# Blocky_Uno.net
KiCad netlist of a schematic drawn in EAGLE
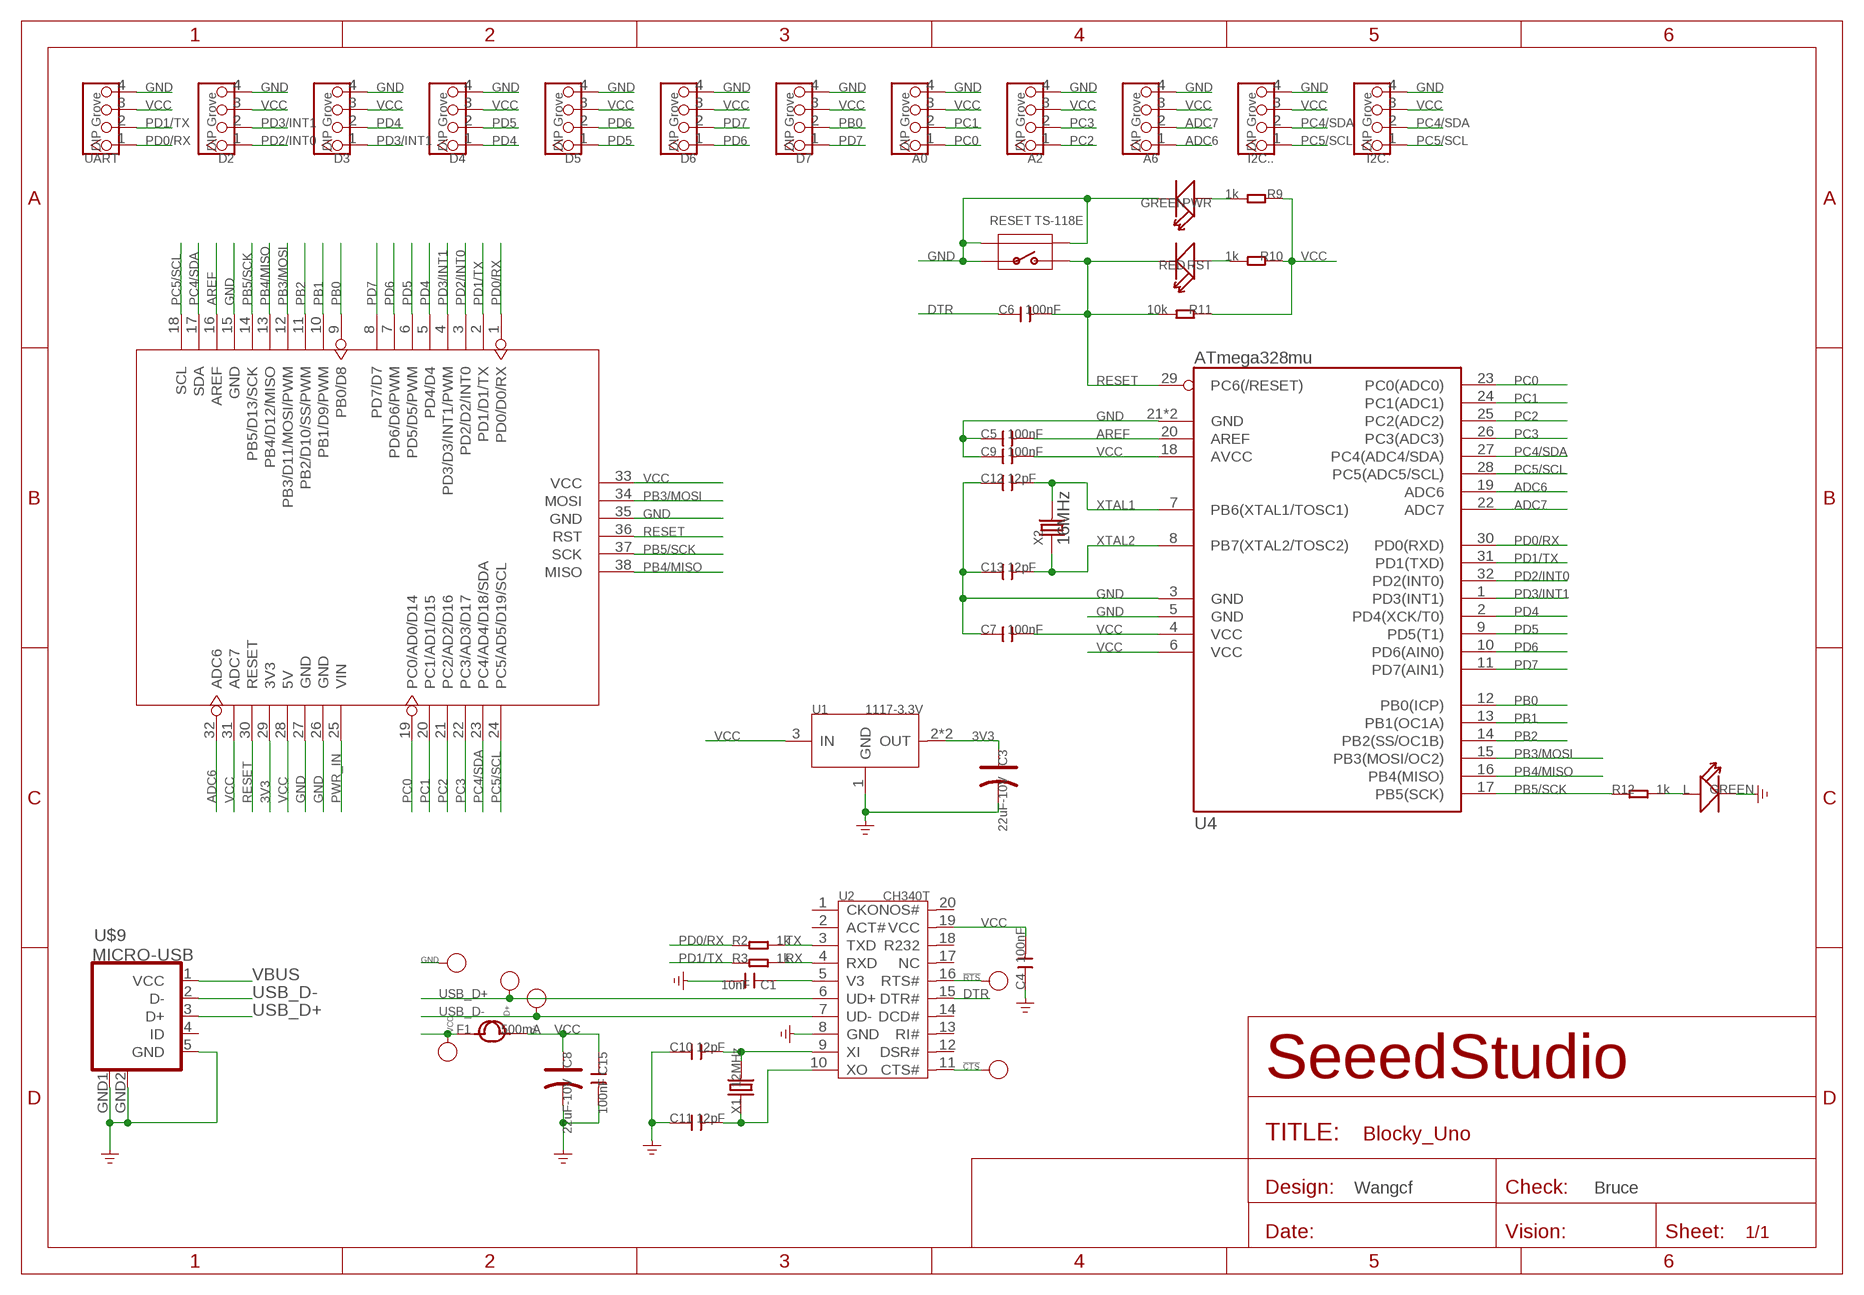
[diagram p0: schematic, sheet 1]

(export (version "E")
  (design (tool "Eeschema 10.0.6"))
  (components
    (comp (ref "!CTS")
      (value "PAD-TEST-POINT'4545'")
      (footprint "eagle-import:TP_4545")
      (fields (field (name "PARTNO") "DNP"))
      (libsource (lib "eagle-import") (part "PAD-TEST-POINT'4545'"))
    )
    (comp (ref "!RTS")
      (value "PAD-TEST-POINT'4545'")
      (footprint "eagle-import:TP_4545")
      (fields (field (name "PARTNO") "DNP"))
      (libsource (lib "eagle-import") (part "PAD-TEST-POINT'4545'"))
    )
    (comp (ref "A0")
      (value "DIP Grove")
      (footprint "eagle-import:4P-2.0")
      (libsource (lib "eagle-import") (part "Connector _TWIG-4P-2.0-2.0"))
    )
    (comp (ref "A2")
      (value "DIP Grove")
      (footprint "eagle-import:4P-2.0")
      (libsource (lib "eagle-import") (part "Connector _TWIG-4P-2.0-2.0"))
    )
    (comp (ref "A6")
      (value "DIP Grove")
      (footprint "eagle-import:4P-2.0")
      (libsource (lib "eagle-import") (part "Connector _TWIG-4P-2.0-2.0"))
    )
    (comp (ref "C1")
      (value "10nF")
      (footprint "eagle-import:C0603")
      (libsource (lib "eagle-import") (part "C-0603"))
    )
    (comp (ref "C3")
      (value "22uF-10V")
      (footprint "eagle-import:AVX-A")
      (libsource (lib "eagle-import") (part "CAP-AVX-A"))
    )
    (comp (ref "C4")
      (value "100nF")
      (footprint "eagle-import:C0603")
      (libsource (lib "eagle-import") (part "C-0603"))
    )
    (comp (ref "C5")
      (value "100nF")
      (footprint "eagle-import:C0603")
      (libsource (lib "eagle-import") (part "C-0603"))
    )
    (comp (ref "C6")
      (value "100nF")
      (footprint "eagle-import:C0603")
      (libsource (lib "eagle-import") (part "C-0603"))
    )
    (comp (ref "C7")
      (value "100nF")
      (footprint "eagle-import:C0603")
      (libsource (lib "eagle-import") (part "C-0603"))
    )
    (comp (ref "C8")
      (value "22uF-10V")
      (footprint "eagle-import:AVX-A")
      (libsource (lib "eagle-import") (part "CAP-AVX-A"))
    )
    (comp (ref "C9")
      (value "100nF")
      (footprint "eagle-import:C0603")
      (libsource (lib "eagle-import") (part "C-0603"))
    )
    (comp (ref "C10")
      (value "12pF")
      (footprint "eagle-import:C0603")
      (libsource (lib "eagle-import") (part "C-0603"))
    )
    (comp (ref "C11")
      (value "12pF")
      (footprint "eagle-import:C0603")
      (libsource (lib "eagle-import") (part "C-0603"))
    )
    (comp (ref "C12")
      (value "12pF")
      (footprint "eagle-import:C0603")
      (libsource (lib "eagle-import") (part "C-0603"))
    )
    (comp (ref "C13")
      (value "12pF")
      (footprint "eagle-import:C0603")
      (libsource (lib "eagle-import") (part "C-0603"))
    )
    (comp (ref "C15")
      (value "100nF")
      (footprint "eagle-import:C0603")
      (libsource (lib "eagle-import") (part "C-0603"))
    )
    (comp (ref "D+")
      (value "PAD-TEST-POINT'4545'")
      (footprint "eagle-import:TP_4545")
      (fields (field (name "PARTNO") "DNP"))
      (libsource (lib "eagle-import") (part "PAD-TEST-POINT'4545'"))
    )
    (comp (ref "D-")
      (value "PAD-TEST-POINT'4545'")
      (footprint "eagle-import:TP_4545")
      (fields (field (name "PARTNO") "DNP"))
      (libsource (lib "eagle-import") (part "PAD-TEST-POINT'4545'"))
    )
    (comp (ref "D2")
      (value "DIP Grove")
      (footprint "eagle-import:4P-2.0")
      (libsource (lib "eagle-import") (part "TWIG-4P-2.0-2.0"))
    )
    (comp (ref "D3")
      (value "DIP Grove")
      (footprint "eagle-import:4P-2.0")
      (libsource (lib "eagle-import") (part "TWIG-4P-2.0-2.0"))
    )
    (comp (ref "D4")
      (value "DIP Grove")
      (footprint "eagle-import:4P-2.0")
      (libsource (lib "eagle-import") (part "TWIG-4P-2.0-2.0"))
    )
    (comp (ref "D5")
      (value "DIP Grove")
      (footprint "eagle-import:4P-2.0")
      (libsource (lib "eagle-import") (part "TWIG-4P-2.0-2.0"))
    )
    (comp (ref "D6")
      (value "DIP Grove")
      (footprint "eagle-import:4P-2.0")
      (libsource (lib "eagle-import") (part "TWIG-4P-2.0-2.0"))
    )
    (comp (ref "D7")
      (value "DIP Grove")
      (footprint "eagle-import:4P-2.0")
      (libsource (lib "eagle-import") (part "TWIG-4P-2.0-2.0"))
    )
    (comp (ref "F1")
      (value "500mA")
      (footprint "eagle-import:F1206")
      (libsource (lib "eagle-import") (part "FUSE'1206'"))
    )
    (comp (ref "GND")
      (value "PAD-TEST-POINT'4545'")
      (footprint "eagle-import:TP_4545")
      (fields (field (name "PARTNO") "DNP"))
      (libsource (lib "eagle-import") (part "PAD-TEST-POINT'4545'"))
    )
    (comp (ref "I2C.")
      (value "DIP Grove")
      (footprint "eagle-import:4P-2.0")
      (libsource (lib "eagle-import") (part "TWIG-4P-2.0-2.0"))
    )
    (comp (ref "I2C..")
      (value "DIP Grove")
      (footprint "eagle-import:4P-2.0")
      (libsource (lib "eagle-import") (part "TWIG-4P-2.0-2.0"))
    )
    (comp (ref "L")
      (value "GREEN")
      (footprint "eagle-import:LED-0603")
      (libsource (lib "eagle-import") (part "LED'0603'"))
    )
    (comp (ref "PWR")
      (value "GREEN")
      (footprint "eagle-import:LED-0603")
      (libsource (lib "eagle-import") (part "LED'0603'"))
    )
    (comp (ref "R2")
      (value "1k")
      (footprint "eagle-import:R0603")
      (libsource (lib "eagle-import") (part "R-0603"))
    )
    (comp (ref "R3")
      (value "1k")
      (footprint "eagle-import:R0603")
      (libsource (lib "eagle-import") (part "R-0603"))
    )
    (comp (ref "R9")
      (value "1k")
      (footprint "eagle-import:R0603")
      (libsource (lib "eagle-import") (part "R-0603"))
    )
    (comp (ref "R10")
      (value "1k")
      (footprint "eagle-import:R0603")
      (libsource (lib "eagle-import") (part "R-0603"))
    )
    (comp (ref "R11")
      (value "10k")
      (footprint "eagle-import:R0603")
      (libsource (lib "eagle-import") (part "R-0603"))
    )
    (comp (ref "R12")
      (value "1k")
      (footprint "eagle-import:R0603")
      (libsource (lib "eagle-import") (part "R-0603"))
    )
    (comp (ref "RESET")
      (value "TS-118E")
      (footprint "eagle-import:4P-SMD-7X3.5X3.5H")
      (libsource (lib "eagle-import") (part "BUTTON-4P-REINFORCE'TS-1188E'"))
    )
    (comp (ref "RST")
      (value "RED")
      (footprint "eagle-import:LED-0603")
      (libsource (lib "eagle-import") (part "LED'0603'"))
    )
    (comp (ref "U$9")
      (value "MICRO-USB")
      (footprint "eagle-import:MICRO-USB")
      (libsource (lib "eagle-import") (part "MICRO-USB"))
    )
    (comp (ref "U1")
      (value "1117-3.3V")
      (footprint "eagle-import:SOT89")
      (libsource (lib "eagle-import") (part "LD1117'SOT89'"))
    )
    (comp (ref "U2")
      (value "CH340T")
      (footprint "eagle-import:SSOP20")
      (libsource (lib "eagle-import") (part "CH340T"))
    )
    (comp (ref "U3")
      (value "ARDUINO-38P")
      (footprint "eagle-import:ARDUINO-38P")
      (libsource (lib "eagle-import") (part "ARDUINO-38P"))
    )
    (comp (ref "U4")
      (value "ATmega328mu")
      (footprint "eagle-import:MLF32X-W_HEAT")
      (libsource (lib "eagle-import") (part "ATMEGA8/168/328MLF"))
    )
    (comp (ref "UART")
      (value "DIP Grove")
      (footprint "eagle-import:4P-2.0")
      (libsource (lib "eagle-import") (part "TWIG-4P-2.0-2.0"))
    )
    (comp (ref "VCC")
      (value "PAD-TEST-POINT'4545'")
      (footprint "eagle-import:TP_4545")
      (fields (field (name "PARTNO") "DNP"))
      (libsource (lib "eagle-import") (part "PAD-TEST-POINT'4545'"))
    )
    (comp (ref "X1")
      (value "12MHz")
      (footprint "eagle-import:2P-SMD-5X3.2")
      (libsource (lib "eagle-import") (part "CRYSTAL'5032'"))
    )
    (comp (ref "X2")
      (value "16MHz")
      (footprint "eagle-import:2P-SMD-5X3.2")
      (libsource (lib "eagle-import") (part "CRYSTAL'5032'"))
    )
  )
  (nets
    (net (code "1") (name "/3V3") (class "Default")
      (node (ref "C3") (pin "+") (pinfunction "+_+") (pintype "passive"))
      (node (ref "U1") (pin "2") (pinfunction "OUT_2") (pintype "bidirectional"))
      (node (ref "U1") (pin "4") (pinfunction "OUT_4") (pintype "bidirectional"))
      (node (ref "U3") (pin "29") (pinfunction "3V3_29") (pintype "bidirectional"))
    )
    (net (code "2") (name "/ADC6") (class "Default")
      (node (ref "A6") (pin "1") (pinfunction "1_1") (pintype "bidirectional"))
      (node (ref "U3") (pin "32") (pinfunction "ADC6_32") (pintype "bidirectional"))
      (node (ref "U4") (pin "19") (pinfunction "ADC6_19") (pintype "bidirectional"))
    )
    (net (code "3") (name "/ADC7") (class "Default")
      (node (ref "A6") (pin "2") (pinfunction "2_2") (pintype "bidirectional"))
      (node (ref "U4") (pin "22") (pinfunction "ADC7_22") (pintype "bidirectional"))
    )
    (net (code "4") (name "/AREF") (class "Default")
      (node (ref "C5") (pin "2") (pinfunction "2_2") (pintype "passive"))
      (node (ref "U3") (pin "16") (pinfunction "AREF_16") (pintype "bidirectional"))
      (node (ref "U4") (pin "20") (pinfunction "AREF_20") (pintype "bidirectional"))
    )
    (net (code "5") (name "/DTR") (class "Default")
      (node (ref "C6") (pin "1") (pinfunction "1_1") (pintype "passive"))
      (node (ref "U2") (pin "15") (pinfunction "DTR#_15") (pintype "output"))
    )
    (net (code "6") (name "/NOS#") (class "Default")
      (node (ref "U2") (pin "20") (pinfunction "NOS#_20") (pintype "power_in"))
    )
    (net (code "7") (name "/PB0") (class "Default")
      (node (ref "D7") (pin "2") (pinfunction "2_2") (pintype "bidirectional"))
      (node (ref "U3") (pin "9") (pinfunction "PB0/D8_9") (pintype "bidirectional"))
      (node (ref "U4") (pin "12") (pinfunction "PB0(ICP)_12") (pintype "bidirectional"))
    )
    (net (code "8") (name "/PB1") (class "Default")
      (node (ref "U3") (pin "10") (pinfunction "PB1/D9/PWM_10") (pintype "bidirectional"))
      (node (ref "U4") (pin "13") (pinfunction "PB1(OC1A)_13") (pintype "bidirectional"))
    )
    (net (code "9") (name "/PB2") (class "Default")
      (node (ref "U3") (pin "11") (pinfunction "PB2/D10/SS/PWM_11") (pintype "bidirectional"))
      (node (ref "U4") (pin "14") (pinfunction "PB2(SS/OC1B)_14") (pintype "bidirectional"))
    )
    (net (code "10") (name "/PB3{slash}MOSI") (class "Default")
      (node (ref "U3") (pin "12") (pinfunction "PB3/D11/MOSI/PWM_12") (pintype "bidirectional"))
      (node (ref "U3") (pin "34") (pinfunction "MOSI_34") (pintype "bidirectional"))
      (node (ref "U4") (pin "15") (pinfunction "PB3(MOSI/OC2)_15") (pintype "bidirectional"))
    )
    (net (code "11") (name "/PB4{slash}MISO") (class "Default")
      (node (ref "U3") (pin "13") (pinfunction "PB4/D12/MISO_13") (pintype "bidirectional"))
      (node (ref "U3") (pin "38") (pinfunction "MISO_38") (pintype "bidirectional"))
      (node (ref "U4") (pin "16") (pinfunction "PB4(MISO)_16") (pintype "bidirectional"))
    )
    (net (code "12") (name "/PB5{slash}SCK") (class "Default")
      (node (ref "R12") (pin "1") (pinfunction "1_1") (pintype "passive"))
      (node (ref "U3") (pin "14") (pinfunction "PB5/D13/SCK_14") (pintype "bidirectional"))
      (node (ref "U3") (pin "37") (pinfunction "SCK_37") (pintype "bidirectional"))
      (node (ref "U4") (pin "17") (pinfunction "PB5(SCK)_17") (pintype "bidirectional"))
    )
    (net (code "13") (name "/PC0") (class "Default")
      (node (ref "A0") (pin "1") (pinfunction "1_1") (pintype "bidirectional"))
      (node (ref "U3") (pin "19") (pinfunction "PC0/AD0/D14_19") (pintype "bidirectional"))
      (node (ref "U4") (pin "23") (pinfunction "PC0(ADC0)_23") (pintype "bidirectional"))
    )
    (net (code "14") (name "/PC1") (class "Default")
      (node (ref "A0") (pin "2") (pinfunction "2_2") (pintype "bidirectional"))
      (node (ref "U3") (pin "20") (pinfunction "PC1/AD1/D15_20") (pintype "bidirectional"))
      (node (ref "U4") (pin "24") (pinfunction "PC1(ADC1)_24") (pintype "bidirectional"))
    )
    (net (code "15") (name "/PC2") (class "Default")
      (node (ref "A2") (pin "1") (pinfunction "1_1") (pintype "bidirectional"))
      (node (ref "U3") (pin "21") (pinfunction "PC2/AD2/D16_21") (pintype "bidirectional"))
      (node (ref "U4") (pin "25") (pinfunction "PC2(ADC2)_25") (pintype "bidirectional"))
    )
    (net (code "16") (name "/PC3") (class "Default")
      (node (ref "A2") (pin "2") (pinfunction "2_2") (pintype "bidirectional"))
      (node (ref "U3") (pin "22") (pinfunction "PC3/AD3/D17_22") (pintype "bidirectional"))
      (node (ref "U4") (pin "26") (pinfunction "PC3(ADC3)_26") (pintype "bidirectional"))
    )
    (net (code "17") (name "/PC4{slash}SDA") (class "Default")
      (node (ref "I2C.") (pin "2") (pinfunction "2_2") (pintype "bidirectional"))
      (node (ref "I2C..") (pin "2") (pinfunction "2_2") (pintype "bidirectional"))
      (node (ref "U3") (pin "17") (pinfunction "SDA_17") (pintype "bidirectional"))
      (node (ref "U3") (pin "23") (pinfunction "PC4/AD4/D18/SDA_23") (pintype "bidirectional"))
      (node (ref "U4") (pin "27") (pinfunction "PC4(ADC4/SDA)_27") (pintype "bidirectional"))
    )
    (net (code "18") (name "/PC5{slash}SCL") (class "Default")
      (node (ref "I2C.") (pin "1") (pinfunction "1_1") (pintype "bidirectional"))
      (node (ref "I2C..") (pin "1") (pinfunction "1_1") (pintype "bidirectional"))
      (node (ref "U3") (pin "18") (pinfunction "SCL_18") (pintype "bidirectional"))
      (node (ref "U3") (pin "24") (pinfunction "PC5/AD5/D19/SCL_24") (pintype "bidirectional"))
      (node (ref "U4") (pin "28") (pinfunction "PC5(ADC5/SCL)_28") (pintype "bidirectional"))
    )
    (net (code "19") (name "/PD0{slash}RX") (class "Default")
      (node (ref "R2") (pin "1") (pinfunction "1_1") (pintype "passive"))
      (node (ref "U3") (pin "1") (pinfunction "PD0/D0/RX_1") (pintype "bidirectional"))
      (node (ref "U4") (pin "30") (pinfunction "PD0(RXD)_30") (pintype "bidirectional"))
      (node (ref "UART") (pin "1") (pinfunction "1_1") (pintype "bidirectional"))
    )
    (net (code "20") (name "/PD1{slash}TX") (class "Default")
      (node (ref "R3") (pin "1") (pinfunction "1_1") (pintype "passive"))
      (node (ref "U3") (pin "2") (pinfunction "PD1/D1/TX_2") (pintype "bidirectional"))
      (node (ref "U4") (pin "31") (pinfunction "PD1(TXD)_31") (pintype "bidirectional"))
      (node (ref "UART") (pin "2") (pinfunction "2_2") (pintype "bidirectional"))
    )
    (net (code "21") (name "/PD2{slash}INT0") (class "Default")
      (node (ref "D2") (pin "1") (pinfunction "1_1") (pintype "bidirectional"))
      (node (ref "U3") (pin "3") (pinfunction "PD2/D2/INT0_3") (pintype "bidirectional"))
      (node (ref "U4") (pin "32") (pinfunction "PD2(INT0)_32") (pintype "bidirectional"))
    )
    (net (code "22") (name "/PD3{slash}INT1") (class "Default")
      (node (ref "D2") (pin "2") (pinfunction "2_2") (pintype "bidirectional"))
      (node (ref "D3") (pin "1") (pinfunction "1_1") (pintype "bidirectional"))
      (node (ref "U3") (pin "4") (pinfunction "PD3/D3/INT1/PWM_4") (pintype "bidirectional"))
      (node (ref "U4") (pin "1") (pinfunction "PD3(INT1)_1") (pintype "bidirectional"))
    )
    (net (code "23") (name "/PD4") (class "Default")
      (node (ref "D3") (pin "2") (pinfunction "2_2") (pintype "bidirectional"))
      (node (ref "D4") (pin "1") (pinfunction "1_1") (pintype "bidirectional"))
      (node (ref "U3") (pin "5") (pinfunction "PD4/D4_5") (pintype "bidirectional"))
      (node (ref "U4") (pin "2") (pinfunction "PD4(XCK/T0)_2") (pintype "bidirectional"))
    )
    (net (code "24") (name "/PD5") (class "Default")
      (node (ref "D4") (pin "2") (pinfunction "2_2") (pintype "bidirectional"))
      (node (ref "D5") (pin "1") (pinfunction "1_1") (pintype "bidirectional"))
      (node (ref "U3") (pin "6") (pinfunction "PD5/D5/PWM_6") (pintype "bidirectional"))
      (node (ref "U4") (pin "9") (pinfunction "PD5(T1)_9") (pintype "bidirectional"))
    )
    (net (code "25") (name "/PD6") (class "Default")
      (node (ref "D5") (pin "2") (pinfunction "2_2") (pintype "bidirectional"))
      (node (ref "D6") (pin "1") (pinfunction "1_1") (pintype "bidirectional"))
      (node (ref "U3") (pin "7") (pinfunction "PD6/D6/PWM_7") (pintype "bidirectional"))
      (node (ref "U4") (pin "10") (pinfunction "PD6(AIN0)_10") (pintype "bidirectional"))
    )
    (net (code "26") (name "/PD7") (class "Default")
      (node (ref "D6") (pin "2") (pinfunction "2_2") (pintype "bidirectional"))
      (node (ref "D7") (pin "1") (pinfunction "1_1") (pintype "bidirectional"))
      (node (ref "U3") (pin "8") (pinfunction "PD7/D7_8") (pintype "bidirectional"))
      (node (ref "U4") (pin "11") (pinfunction "PD7(AIN1)_11") (pintype "bidirectional"))
    )
    (net (code "27") (name "/PWR_IN") (class "Default")
      (node (ref "U3") (pin "25") (pinfunction "VIN_25") (pintype "bidirectional"))
    )
    (net (code "28") (name "/RESET") (class "Default")
      (node (ref "C6") (pin "2") (pinfunction "2_2") (pintype "passive"))
      (node (ref "R11") (pin "2") (pinfunction "2_2") (pintype "passive"))
      (node (ref "RESET") (pin "2") (pinfunction "2_2") (pintype "bidirectional"))
      (node (ref "RST") (pin "-") (pinfunction "-_-") (pintype "passive"))
      (node (ref "U3") (pin "30") (pinfunction "RESET_30") (pintype "bidirectional"))
      (node (ref "U3") (pin "36") (pinfunction "RST_36") (pintype "bidirectional"))
      (node (ref "U4") (pin "29") (pinfunction "PC6(/RESET)_29") (pintype "bidirectional"))
    )
    (net (code "29") (name "/RX") (class "Default")
      (node (ref "R3") (pin "2") (pinfunction "2_2") (pintype "passive"))
      (node (ref "U2") (pin "4") (pinfunction "RXD_4") (pintype "input"))
    )
    (net (code "30") (name "/TX") (class "Default")
      (node (ref "R2") (pin "2") (pinfunction "2_2") (pintype "passive"))
      (node (ref "U2") (pin "3") (pinfunction "TXD_3") (pintype "output"))
    )
    (net (code "31") (name "/USB_D+") (class "Default")
      (node (ref "D+") (pin "T") (pinfunction "T_T") (pintype "bidirectional"))
      (node (ref "U$9") (pin "3") (pinfunction "D+_3") (pintype "bidirectional"))
      (node (ref "U2") (pin "6") (pinfunction "UD+_6") (pintype "bidirectional"))
    )
    (net (code "32") (name "/USB_D-") (class "Default")
      (node (ref "D-") (pin "T") (pinfunction "T_T") (pintype "bidirectional"))
      (node (ref "U$9") (pin "2") (pinfunction "D-_2") (pintype "bidirectional"))
      (node (ref "U2") (pin "7") (pinfunction "UD-_7") (pintype "bidirectional"))
    )
    (net (code "33") (name "/VBUS") (class "Default")
      (node (ref "F1") (pin "1") (pinfunction "1_1") (pintype "bidirectional"))
      (node (ref "U$9") (pin "1") (pinfunction "VCC_1") (pintype "power_in"))
      (node (ref "VCC") (pin "T") (pinfunction "T_T") (pintype "bidirectional"))
    )
    (net (code "34") (name "/VCC") (class "Default")
      (node (ref "A0") (pin "3") (pinfunction "3_3") (pintype "bidirectional"))
      (node (ref "A2") (pin "3") (pinfunction "3_3") (pintype "bidirectional"))
      (node (ref "A6") (pin "3") (pinfunction "3_3") (pintype "bidirectional"))
      (node (ref "C15") (pin "1") (pinfunction "1_1") (pintype "passive"))
      (node (ref "C4") (pin "2") (pinfunction "2_2") (pintype "passive"))
      (node (ref "C7") (pin "2") (pinfunction "2_2") (pintype "passive"))
      (node (ref "C8") (pin "+") (pinfunction "+_+") (pintype "passive"))
      (node (ref "C9") (pin "2") (pinfunction "2_2") (pintype "passive"))
      (node (ref "D2") (pin "3") (pinfunction "3_3") (pintype "bidirectional"))
      (node (ref "D3") (pin "3") (pinfunction "3_3") (pintype "bidirectional"))
      (node (ref "D4") (pin "3") (pinfunction "3_3") (pintype "bidirectional"))
      (node (ref "D5") (pin "3") (pinfunction "3_3") (pintype "bidirectional"))
      (node (ref "D6") (pin "3") (pinfunction "3_3") (pintype "bidirectional"))
      (node (ref "D7") (pin "3") (pinfunction "3_3") (pintype "bidirectional"))
      (node (ref "F1") (pin "2") (pinfunction "2_2") (pintype "bidirectional"))
      (node (ref "I2C.") (pin "3") (pinfunction "3_3") (pintype "bidirectional"))
      (node (ref "I2C..") (pin "3") (pinfunction "3_3") (pintype "bidirectional"))
      (node (ref "R10") (pin "1") (pinfunction "1_1") (pintype "passive"))
      (node (ref "R11") (pin "1") (pinfunction "1_1") (pintype "passive"))
      (node (ref "R9") (pin "1") (pinfunction "1_1") (pintype "passive"))
      (node (ref "U1") (pin "3") (pinfunction "IN_3") (pintype "bidirectional"))
      (node (ref "U2") (pin "19") (pinfunction "VCC_19") (pintype "power_in"))
      (node (ref "U3") (pin "28") (pinfunction "5V_28") (pintype "bidirectional"))
      (node (ref "U3") (pin "31") (pinfunction "ADC7_31") (pintype "bidirectional"))
      (node (ref "U3") (pin "33") (pinfunction "VCC_33") (pintype "bidirectional"))
      (node (ref "U4") (pin "18") (pinfunction "AVCC_18") (pintype "bidirectional"))
      (node (ref "U4") (pin "4") (pinfunction "VCC_4") (pintype "bidirectional"))
      (node (ref "U4") (pin "6") (pinfunction "VCC_6") (pintype "bidirectional"))
      (node (ref "UART") (pin "3") (pinfunction "3_3") (pintype "bidirectional"))
    )
    (net (code "35") (name "/XTAL1") (class "Default")
      (node (ref "C12") (pin "2") (pinfunction "2_2") (pintype "passive"))
      (node (ref "U4") (pin "7") (pinfunction "PB6(XTAL1/TOSC1)_7") (pintype "bidirectional"))
      (node (ref "X2") (pin "2") (pinfunction "2_2") (pintype "passive"))
    )
    (net (code "36") (name "/XTAL2") (class "Default")
      (node (ref "C13") (pin "2") (pinfunction "2_2") (pintype "passive"))
      (node (ref "U4") (pin "8") (pinfunction "PB7(XTAL2/TOSC2)_8") (pintype "bidirectional"))
      (node (ref "X2") (pin "1") (pinfunction "1_1") (pintype "passive"))
    )
    (net (code "37") (name "GND_POWER") (class "Default")
      (node (ref "A0") (pin "4") (pinfunction "4_4") (pintype "bidirectional"))
      (node (ref "A2") (pin "4") (pinfunction "4_4") (pintype "bidirectional"))
      (node (ref "A6") (pin "4") (pinfunction "4_4") (pintype "bidirectional"))
      (node (ref "C1") (pin "2") (pinfunction "2_2") (pintype "passive"))
      (node (ref "C10") (pin "1") (pinfunction "1_1") (pintype "passive"))
      (node (ref "C11") (pin "1") (pinfunction "1_1") (pintype "passive"))
      (node (ref "C12") (pin "1") (pinfunction "1_1") (pintype "passive"))
      (node (ref "C13") (pin "1") (pinfunction "1_1") (pintype "passive"))
      (node (ref "C15") (pin "2") (pinfunction "2_2") (pintype "passive"))
      (node (ref "C3") (pin "-") (pinfunction "-_-") (pintype "passive"))
      (node (ref "C4") (pin "1") (pinfunction "1_1") (pintype "passive"))
      (node (ref "C5") (pin "1") (pinfunction "1_1") (pintype "passive"))
      (node (ref "C7") (pin "1") (pinfunction "1_1") (pintype "passive"))
      (node (ref "C8") (pin "-") (pinfunction "-_-") (pintype "passive"))
      (node (ref "C9") (pin "1") (pinfunction "1_1") (pintype "passive"))
      (node (ref "D2") (pin "4") (pinfunction "4_4") (pintype "bidirectional"))
      (node (ref "D3") (pin "4") (pinfunction "4_4") (pintype "bidirectional"))
      (node (ref "D4") (pin "4") (pinfunction "4_4") (pintype "bidirectional"))
      (node (ref "D5") (pin "4") (pinfunction "4_4") (pintype "bidirectional"))
      (node (ref "D6") (pin "4") (pinfunction "4_4") (pintype "bidirectional"))
      (node (ref "D7") (pin "4") (pinfunction "4_4") (pintype "bidirectional"))
      (node (ref "GND") (pin "T") (pinfunction "T_T") (pintype "bidirectional"))
      (node (ref "I2C.") (pin "4") (pinfunction "4_4") (pintype "bidirectional"))
      (node (ref "I2C..") (pin "4") (pinfunction "4_4") (pintype "bidirectional"))
      (node (ref "L") (pin "-") (pinfunction "-_-") (pintype "passive"))
      (node (ref "PWR") (pin "-") (pinfunction "-_-") (pintype "passive"))
      (node (ref "RESET") (pin "1") (pinfunction "1_1") (pintype "bidirectional"))
      (node (ref "RESET") (pin "S1") (pinfunction "S1_S1") (pintype "bidirectional"))
      (node (ref "RESET") (pin "S2") (pinfunction "S2_S2") (pintype "bidirectional"))
      (node (ref "U$9") (pin "5") (pinfunction "GND_5") (pintype "power_in"))
      (node (ref "U$9") (pin "GND1") (pinfunction "GND_GND1") (pintype "power_in"))
      (node (ref "U$9") (pin "GND2") (pinfunction "GND_GND2") (pintype "power_in"))
      (node (ref "U1") (pin "1") (pinfunction "GND_1") (pintype "bidirectional"))
      (node (ref "U2") (pin "8") (pinfunction "GND_8") (pintype "power_in"))
      (node (ref "U3") (pin "15") (pinfunction "GND_15") (pintype "bidirectional"))
      (node (ref "U3") (pin "26") (pinfunction "GND_26") (pintype "bidirectional"))
      (node (ref "U3") (pin "27") (pinfunction "GND_27") (pintype "bidirectional"))
      (node (ref "U3") (pin "35") (pinfunction "GND_35") (pintype "bidirectional"))
      (node (ref "U4") (pin "21") (pinfunction "GND_21") (pintype "bidirectional"))
      (node (ref "U4") (pin "3") (pinfunction "GND_3") (pintype "bidirectional"))
      (node (ref "U4") (pin "5") (pinfunction "GND_5") (pintype "bidirectional"))
      (node (ref "U4") (pin "HEAT") (pinfunction "GND_HEAT") (pintype "bidirectional"))
      (node (ref "UART") (pin "4") (pinfunction "4_4") (pintype "bidirectional"))
    )
    (net (code "38") (name "Net-(L-Pad+)") (class "Default")
      (node (ref "L") (pin "+") (pinfunction "+_+") (pintype "passive"))
      (node (ref "R12") (pin "2") (pinfunction "2_2") (pintype "passive"))
    )
    (net (code "39") (name "Net-(PWR-Pad+)") (class "Default")
      (node (ref "PWR") (pin "+") (pinfunction "+_+") (pintype "passive"))
      (node (ref "R9") (pin "2") (pinfunction "2_2") (pintype "passive"))
    )
    (net (code "40") (name "Net-(R10-Pad2)") (class "Default")
      (node (ref "R10") (pin "2") (pinfunction "2_2") (pintype "passive"))
      (node (ref "RST") (pin "+") (pinfunction "+_+") (pintype "passive"))
    )
    (net (code "41") (name "Net-(U2-CTS#)") (class "Default")
      (node (ref "!CTS") (pin "T") (pinfunction "T_T") (pintype "bidirectional"))
      (node (ref "U2") (pin "11") (pinfunction "CTS#_11") (pintype "input"))
    )
    (net (code "42") (name "Net-(U2-RTS#)") (class "Default")
      (node (ref "!RTS") (pin "T") (pinfunction "T_T") (pintype "bidirectional"))
      (node (ref "U2") (pin "16") (pinfunction "RTS#_16") (pintype "output"))
    )
    (net (code "43") (name "Net-(U2-V3)") (class "Default")
      (node (ref "C1") (pin "1") (pinfunction "1_1") (pintype "passive"))
      (node (ref "U2") (pin "5") (pinfunction "V3_5") (pintype "power_in"))
    )
    (net (code "44") (name "Net-(U2-XI)") (class "Default")
      (node (ref "C10") (pin "2") (pinfunction "2_2") (pintype "passive"))
      (node (ref "U2") (pin "9") (pinfunction "XI_9") (pintype "input"))
      (node (ref "X1") (pin "2") (pinfunction "2_2") (pintype "passive"))
    )
    (net (code "45") (name "Net-(U2-XO)") (class "Default")
      (node (ref "C11") (pin "2") (pinfunction "2_2") (pintype "passive"))
      (node (ref "U2") (pin "10") (pinfunction "XO_10") (pintype "output"))
      (node (ref "X1") (pin "1") (pinfunction "1_1") (pintype "passive"))
    )
    (net (code "46") (name "unconnected-(U$9-ID-Pad4)") (class "Default")
      (node (ref "U$9") (pin "4") (pinfunction "ID_4") (pintype "bidirectional"))
    )
    (net (code "47") (name "unconnected-(U2-ACT#-Pad2)") (class "Default")
      (node (ref "U2") (pin "2") (pinfunction "ACT#_2") (pintype "output"))
    )
    (net (code "48") (name "unconnected-(U2-CKO-Pad1)") (class "Default")
      (node (ref "U2") (pin "1") (pinfunction "CKO_1") (pintype "output"))
    )
    (net (code "49") (name "unconnected-(U2-DCD#-Pad14)") (class "Default")
      (node (ref "U2") (pin "14") (pinfunction "DCD#_14") (pintype "input"))
    )
    (net (code "50") (name "unconnected-(U2-DSR#-Pad12)") (class "Default")
      (node (ref "U2") (pin "12") (pinfunction "DSR#_12") (pintype "input"))
    )
    (net (code "51") (name "unconnected-(U2-NC-Pad17)") (class "Default")
      (node (ref "U2") (pin "17") (pinfunction "NC_17") (pintype "no_connect"))
    )
    (net (code "52") (name "unconnected-(U2-R232-Pad18)") (class "Default")
      (node (ref "U2") (pin "18") (pinfunction "R232_18") (pintype "input"))
    )
    (net (code "53") (name "unconnected-(U2-RI#-Pad13)") (class "Default")
      (node (ref "U2") (pin "13") (pinfunction "RI#_13") (pintype "input"))
    )
  )
)
